# 17_RK3568_VO_Interface_1.net
KiCad netlist of a schematic drawn in Altium Designer
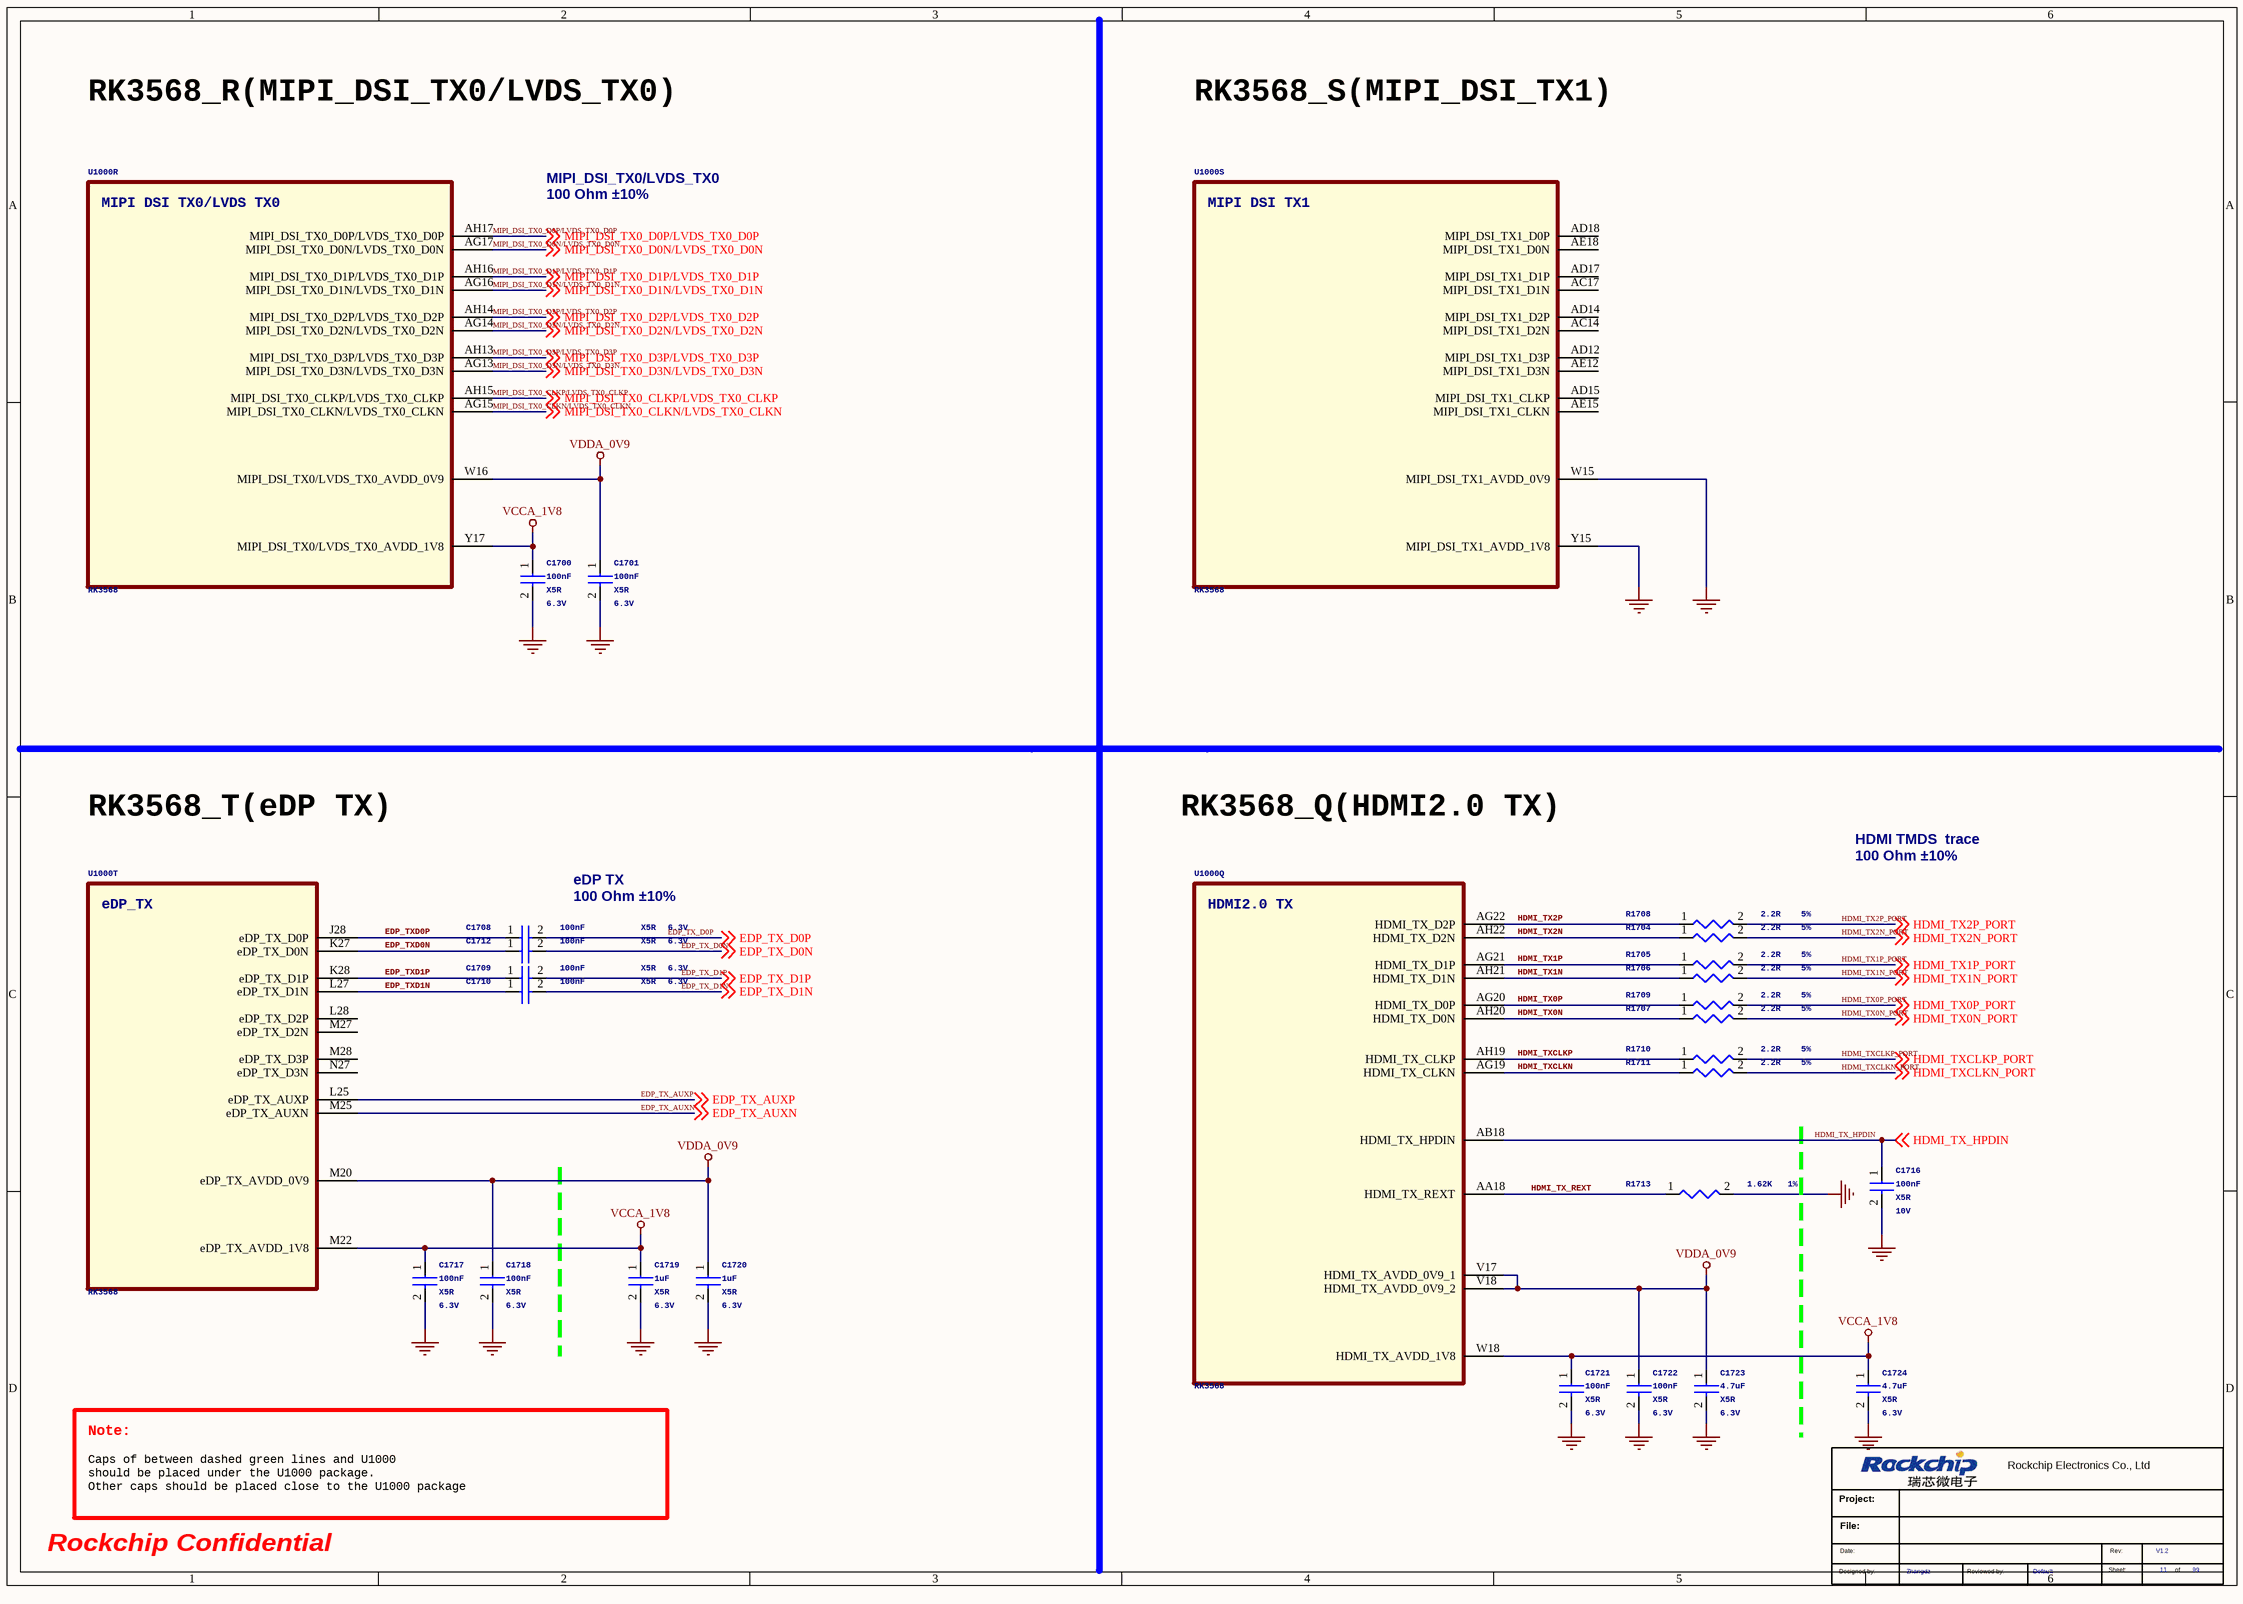
[diagram p0: 17.RK3568_VO Interface_1.SchDoc]

(export (version "E")
  (design (tool "Eeschema 10.0.6"))
  (components
    (comp (ref "*")
      (value "Rockchip_new")
      (fields
        (field (name "SCHEMATIC PAGE COUNT") "99")
        (field (name "SCHEMATIC PAGE NUMBER") "11")
        (field (name "DESIGNER") "Zhangdz")
        (field (name "REVISION") "V1.2")
        (field (name "CHECK") "Default")
      )
      (libsource (lib "*") (part "Rockchip_new"))
    )
    (comp (ref "C1700")
      (value "100nF")
      (footprint "C0201")
      (description "cap,100.00nF,+/-10%,6.3V,X5R,C0201")
      (fields
        (field (name "VOLTAGE") "6.3V")
        (field (name "DIELECTRIC") "X5R")
        (field (name "TOLERANCE") "10%")
        (field (name "MANUFACTURER") "TDK")
        (field (name "CREATED BY") "JJJ")
      )
      (libsource (lib "*") (part "CAP NP"))
    )
    (comp (ref "C1701")
      (value "100nF")
      (footprint "C0201")
      (description "cap,100.00nF,+/-10%,6.3V,X5R,C0201")
      (fields
        (field (name "VOLTAGE") "6.3V")
        (field (name "DIELECTRIC") "X5R")
        (field (name "MANUFACTURER") "TDK")
        (field (name "TOLERANCE") "10%")
        (field (name "CREATED BY") "JJJ")
      )
      (libsource (lib "*") (part "CAP NP"))
    )
    (comp (ref "C1708")
      (value "100nF")
      (footprint "C0201")
      (description "cap,100.00nF,+/-10%,6.3V,X5R,C0201")
      (fields
        (field (name "VOLTAGE") "6.3V")
        (field (name "DIELECTRIC") "X5R")
        (field (name "MANUFACTURER") "TDK")
        (field (name "TOLERANCE") "10%")
        (field (name "CREATED BY") "JJJ")
      )
      (libsource (lib "*") (part "CAP NP"))
    )
    (comp (ref "C1709")
      (value "100nF")
      (footprint "C0201")
      (description "cap,100.00nF,+/-10%,6.3V,X5R,C0201")
      (fields
        (field (name "VOLTAGE") "6.3V")
        (field (name "DIELECTRIC") "X5R")
        (field (name "MANUFACTURER") "TDK")
        (field (name "TOLERANCE") "10%")
        (field (name "CREATED BY") "JJJ")
      )
      (libsource (lib "*") (part "CAP NP"))
    )
    (comp (ref "C1710")
      (value "100nF")
      (footprint "C0201")
      (description "cap,100.00nF,+/-10%,6.3V,X5R,C0201")
      (fields
        (field (name "VOLTAGE") "6.3V")
        (field (name "DIELECTRIC") "X5R")
        (field (name "TOLERANCE") "10%")
        (field (name "MANUFACTURER") "TDK")
        (field (name "CREATED BY") "JJJ")
      )
      (libsource (lib "*") (part "CAP NP"))
    )
    (comp (ref "C1712")
      (value "100nF")
      (footprint "C0201")
      (description "cap,100.00nF,+/-10%,6.3V,X5R,C0201")
      (fields
        (field (name "VOLTAGE") "6.3V")
        (field (name "DIELECTRIC") "X5R")
        (field (name "TOLERANCE") "10%")
        (field (name "MANUFACTURER") "TDK")
        (field (name "CREATED BY") "JJJ")
      )
      (libsource (lib "*") (part "CAP NP"))
    )
    (comp (ref "C1716")
      (value "100nF")
      (footprint "C0402")
      (description "cap,100.00nF,+/-10%,10V,X5R,C0402")
      (fields
        (field (name "VOLTAGE") "10V")
        (field (name "DIELECTRIC") "X5R")
        (field (name "TOLERANCE") "10%")
        (field (name "MANUFACTURER") "TDK")
        (field (name "CREATED BY") "JJJ")
      )
      (libsource (lib "*") (part "CAP NP"))
    )
    (comp (ref "C1717")
      (value "100nF")
      (footprint "C0201")
      (description "cap,100.00nF,+/-10%,6.3V,X5R,C0201")
      (fields
        (field (name "VOLTAGE") "6.3V")
        (field (name "DIELECTRIC") "X5R")
        (field (name "TOLERANCE") "10%")
        (field (name "MANUFACTURER") "TDK")
        (field (name "CREATED BY") "JJJ")
      )
      (libsource (lib "*") (part "CAP NP"))
    )
    (comp (ref "C1718")
      (value "100nF")
      (footprint "C0201")
      (description "cap,100.00nF,+/-10%,6.3V,X5R,C0201")
      (fields
        (field (name "VOLTAGE") "6.3V")
        (field (name "DIELECTRIC") "X5R")
        (field (name "MANUFACTURER") "TDK")
        (field (name "TOLERANCE") "10%")
        (field (name "CREATED BY") "JJJ")
      )
      (libsource (lib "*") (part "CAP NP"))
    )
    (comp (ref "C1719")
      (value "1uF")
      (footprint "C0402")
      (description "cap,1.00uF,+/-10%,6.3V,X5R,C0402")
      (fields
        (field (name "VOLTAGE") "6.3V")
        (field (name "DIELECTRIC") "X5R")
        (field (name "TOLERANCE") "10%")
        (field (name "MANUFACTURER") "TDK")
        (field (name "CREATED BY") "JJJ")
      )
      (libsource (lib "*") (part "CAP NP"))
    )
    (comp (ref "C1720")
      (value "1uF")
      (footprint "C0402")
      (description "cap,1.00uF,+/-10%,6.3V,X5R,C0402")
      (fields
        (field (name "VOLTAGE") "6.3V")
        (field (name "DIELECTRIC") "X5R")
        (field (name "MANUFACTURER") "TDK")
        (field (name "TOLERANCE") "10%")
        (field (name "CREATED BY") "JJJ")
      )
      (libsource (lib "*") (part "CAP NP"))
    )
    (comp (ref "C1721")
      (value "100nF")
      (footprint "C0201")
      (description "cap,100.00nF,+/-10%,6.3V,X5R,C0201")
      (fields
        (field (name "VOLTAGE") "6.3V")
        (field (name "DIELECTRIC") "X5R")
        (field (name "MANUFACTURER") "TDK")
        (field (name "TOLERANCE") "10%")
        (field (name "CREATED BY") "JJJ")
      )
      (libsource (lib "*") (part "CAP NP"))
    )
    (comp (ref "C1722")
      (value "100nF")
      (footprint "C0201")
      (description "cap,100.00nF,+/-10%,6.3V,X5R,C0201")
      (fields
        (field (name "VOLTAGE") "6.3V")
        (field (name "DIELECTRIC") "X5R")
        (field (name "TOLERANCE") "10%")
        (field (name "MANUFACTURER") "TDK")
        (field (name "CREATED BY") "JJJ")
      )
      (libsource (lib "*") (part "CAP NP"))
    )
    (comp (ref "C1723")
      (value "4.7uF")
      (footprint "C0402")
      (description "cap,4.70uF,+/-10%,6.3V,X5R,C0402")
      (fields
        (field (name "VOLTAGE") "6.3V")
        (field (name "DIELECTRIC") "X5R")
        (field (name "TOLERANCE") "10%")
        (field (name "MANUFACTURER") "TDK")
        (field (name "CREATED BY") "JJJ")
      )
      (libsource (lib "*") (part "CAP NP"))
    )
    (comp (ref "C1724")
      (value "4.7uF")
      (footprint "C0402")
      (description "cap,4.70uF,+/-10%,6.3V,X5R,C0402")
      (fields
        (field (name "VOLTAGE") "6.3V")
        (field (name "DIELECTRIC") "X5R")
        (field (name "MANUFACTURER") "TDK")
        (field (name "TOLERANCE") "10%")
        (field (name "CREATED BY") "JJJ")
      )
      (libsource (lib "*") (part "CAP NP"))
    )
    (comp (ref "R1704")
      (value "2.2R")
      (footprint "R0402")
      (description "通用厚膜电阻,2R2,+/-5%,R0402,1/16W.")
      (fields
        (field (name "TOLERANCE") "5%")
        (field (name "MANUFACTURER") "YAGEO")
        (field (name "CREATED BY") "YTL")
      )
      (libsource (lib "*") (part "RESISTOR"))
    )
    (comp (ref "R1705")
      (value "2.2R")
      (footprint "R0402")
      (description "通用厚膜电阻,2R2,+/-5%,R0402,1/16W.")
      (fields
        (field (name "TOLERANCE") "5%")
        (field (name "MANUFACTURER") "YAGEO")
        (field (name "CREATED BY") "YTL")
      )
      (libsource (lib "*") (part "RESISTOR"))
    )
    (comp (ref "R1706")
      (value "2.2R")
      (footprint "R0402")
      (description "通用厚膜电阻,2R2,+/-5%,R0402,1/16W.")
      (fields
        (field (name "TOLERANCE") "5%")
        (field (name "MANUFACTURER") "YAGEO")
        (field (name "CREATED BY") "YTL")
      )
      (libsource (lib "*") (part "RESISTOR"))
    )
    (comp (ref "R1707")
      (value "2.2R")
      (footprint "R0402")
      (description "通用厚膜电阻,2R2,+/-5%,R0402,1/16W.")
      (fields
        (field (name "TOLERANCE") "5%")
        (field (name "MANUFACTURER") "YAGEO")
        (field (name "CREATED BY") "YTL")
      )
      (libsource (lib "*") (part "RESISTOR"))
    )
    (comp (ref "R1708")
      (value "2.2R")
      (footprint "R0402")
      (description "通用厚膜电阻,2R2,+/-5%,R0402,1/16W.")
      (fields
        (field (name "TOLERANCE") "5%")
        (field (name "MANUFACTURER") "YAGEO")
        (field (name "CREATED BY") "YTL")
      )
      (libsource (lib "*") (part "RESISTOR"))
    )
    (comp (ref "R1709")
      (value "2.2R")
      (footprint "R0402")
      (description "通用厚膜电阻,2R2,+/-5%,R0402,1/16W.")
      (fields
        (field (name "TOLERANCE") "5%")
        (field (name "MANUFACTURER") "YAGEO")
        (field (name "CREATED BY") "YTL")
      )
      (libsource (lib "*") (part "RESISTOR"))
    )
    (comp (ref "R1710")
      (value "2.2R")
      (footprint "R0402")
      (description "通用厚膜电阻,2R2,+/-5%,R0402,1/16W.")
      (fields
        (field (name "TOLERANCE") "5%")
        (field (name "MANUFACTURER") "YAGEO")
        (field (name "CREATED BY") "YTL")
      )
      (libsource (lib "*") (part "RESISTOR"))
    )
    (comp (ref "R1711")
      (value "2.2R")
      (footprint "R0402")
      (description "通用厚膜电阻,2R2,+/-5%,R0402,1/16W.")
      (fields
        (field (name "TOLERANCE") "5%")
        (field (name "MANUFACTURER") "YAGEO")
        (field (name "CREATED BY") "YTL")
      )
      (libsource (lib "*") (part "RESISTOR"))
    )
    (comp (ref "R1713")
      (value "1.62K")
      (footprint "R0201")
      (description "通用厚膜电阻,1K62,+/-1%,R0201,1/20W.")
      (fields
        (field (name "TOLERANCE") "1%")
        (field (name "MANUFACTURER") "YAGEO")
        (field (name "CREATED BY") "YTL")
      )
      (libsource (lib "*") (part "RESISTOR"))
    )
    (comp (ref "U1000")
      (value "RK3568")
      (footprint "BGA636_19R00X19R00X1R20")
      (description "ROCKCHIP SOC")
      (fields (field (name "MANUFACTURER") "Rockchip (瑞芯微)") (field (name "CREATED BY") "JJJ"))
      (libsource (lib "*") (part "SOC_RK3568"))
    )
  )
  (nets
    (net (code "1") (name "/EDP_TXD0N") (class "Default")
      (node (ref "C1712") (pin "1") (pinfunction "1_1") (pintype "passive"))
      (node (ref "U1000") (pin "K27") (pinfunction "eDP_TX_D0N_K27") (pintype "passive"))
    )
    (net (code "2") (name "/EDP_TXD0P") (class "Default")
      (node (ref "C1708") (pin "1") (pinfunction "1_1") (pintype "passive"))
      (node (ref "U1000") (pin "J28") (pinfunction "eDP_TX_D0P_J28") (pintype "passive"))
    )
    (net (code "3") (name "/EDP_TXD1N") (class "Default")
      (node (ref "C1710") (pin "1") (pinfunction "1_1") (pintype "passive"))
      (node (ref "U1000") (pin "L27") (pinfunction "eDP_TX_D1N_L27") (pintype "passive"))
    )
    (net (code "4") (name "/EDP_TXD1P") (class "Default")
      (node (ref "C1709") (pin "1") (pinfunction "1_1") (pintype "passive"))
      (node (ref "U1000") (pin "K28") (pinfunction "eDP_TX_D1P_K28") (pintype "passive"))
    )
    (net (code "5") (name "/HDMI_TX0N") (class "Default")
      (node (ref "R1707") (pin "1") (pinfunction "1_1") (pintype "passive"))
      (node (ref "U1000") (pin "AH20") (pinfunction "HDMI_TX_D0N_AH20") (pintype "passive"))
    )
    (net (code "6") (name "/HDMI_TX0P") (class "Default")
      (node (ref "R1709") (pin "1") (pinfunction "1_1") (pintype "passive"))
      (node (ref "U1000") (pin "AG20") (pinfunction "HDMI_TX_D0P_AG20") (pintype "passive"))
    )
    (net (code "7") (name "/HDMI_TX1N") (class "Default")
      (node (ref "R1706") (pin "1") (pinfunction "1_1") (pintype "passive"))
      (node (ref "U1000") (pin "AH21") (pinfunction "HDMI_TX_D1N_AH21") (pintype "passive"))
    )
    (net (code "8") (name "/HDMI_TX1P") (class "Default")
      (node (ref "R1705") (pin "1") (pinfunction "1_1") (pintype "passive"))
      (node (ref "U1000") (pin "AG21") (pinfunction "HDMI_TX_D1P_AG21") (pintype "passive"))
    )
    (net (code "9") (name "/HDMI_TX2N") (class "Default")
      (node (ref "R1704") (pin "1") (pinfunction "1_1") (pintype "passive"))
      (node (ref "U1000") (pin "AH22") (pinfunction "HDMI_TX_D2N_AH22") (pintype "passive"))
    )
    (net (code "10") (name "/HDMI_TX2P") (class "Default")
      (node (ref "R1708") (pin "1") (pinfunction "1_1") (pintype "passive"))
      (node (ref "U1000") (pin "AG22") (pinfunction "HDMI_TX_D2P_AG22") (pintype "passive"))
    )
    (net (code "11") (name "/HDMI_TXCLKN") (class "Default")
      (node (ref "R1711") (pin "1") (pinfunction "1_1") (pintype "passive"))
      (node (ref "U1000") (pin "AG19") (pinfunction "HDMI_TX_CLKN_AG19") (pintype "passive"))
    )
    (net (code "12") (name "/HDMI_TXCLKP") (class "Default")
      (node (ref "R1710") (pin "1") (pinfunction "1_1") (pintype "passive"))
      (node (ref "U1000") (pin "AH19") (pinfunction "HDMI_TX_CLKP_AH19") (pintype "passive"))
    )
    (net (code "13") (name "/HDMI_TX_REXT") (class "Default")
      (node (ref "R1713") (pin "1") (pinfunction "1_1") (pintype "passive"))
      (node (ref "U1000") (pin "AA18") (pinfunction "HDMI_TX_REXT_AA18") (pintype "passive"))
    )
    (net (code "14") (name "EDP_TX_AUXN") (class "Default")
      (node (ref "U1000") (pin "M25") (pinfunction "eDP_TX_AUXN_M25") (pintype "passive"))
    )
    (net (code "15") (name "EDP_TX_AUXP") (class "Default")
      (node (ref "U1000") (pin "L25") (pinfunction "eDP_TX_AUXP_L25") (pintype "passive"))
    )
    (net (code "16") (name "EDP_TX_D0N") (class "Default")
      (node (ref "C1712") (pin "2") (pinfunction "2_2") (pintype "passive"))
    )
    (net (code "17") (name "EDP_TX_D0P") (class "Default")
      (node (ref "C1708") (pin "2") (pinfunction "2_2") (pintype "passive"))
    )
    (net (code "18") (name "EDP_TX_D1N") (class "Default")
      (node (ref "C1710") (pin "2") (pinfunction "2_2") (pintype "passive"))
    )
    (net (code "19") (name "EDP_TX_D1P") (class "Default")
      (node (ref "C1709") (pin "2") (pinfunction "2_2") (pintype "passive"))
    )
    (net (code "20") (name "GND") (class "Default")
      (node (ref "C1700") (pin "2") (pinfunction "2_2") (pintype "passive"))
      (node (ref "C1701") (pin "2") (pinfunction "2_2") (pintype "passive"))
      (node (ref "C1716") (pin "2") (pinfunction "2_2") (pintype "passive"))
      (node (ref "C1717") (pin "2") (pinfunction "2_2") (pintype "passive"))
      (node (ref "C1718") (pin "2") (pinfunction "2_2") (pintype "passive"))
      (node (ref "C1719") (pin "2") (pinfunction "2_2") (pintype "passive"))
      (node (ref "C1720") (pin "2") (pinfunction "2_2") (pintype "passive"))
      (node (ref "C1721") (pin "2") (pinfunction "2_2") (pintype "passive"))
      (node (ref "C1722") (pin "2") (pinfunction "2_2") (pintype "passive"))
      (node (ref "C1723") (pin "2") (pinfunction "2_2") (pintype "passive"))
      (node (ref "C1724") (pin "2") (pinfunction "2_2") (pintype "passive"))
      (node (ref "R1713") (pin "2") (pinfunction "2_2") (pintype "passive"))
      (node (ref "U1000") (pin "W15") (pinfunction "MIPI_DSI_TX1_AVDD_0V9_W15") (pintype "passive"))
      (node (ref "U1000") (pin "Y15") (pinfunction "MIPI_DSI_TX1_AVDD_1V8_Y15") (pintype "passive"))
    )
    (net (code "21") (name "HDMI_TX0N_PORT") (class "Default")
      (node (ref "R1707") (pin "2") (pinfunction "2_2") (pintype "passive"))
    )
    (net (code "22") (name "HDMI_TX0P_PORT") (class "Default")
      (node (ref "R1709") (pin "2") (pinfunction "2_2") (pintype "passive"))
    )
    (net (code "23") (name "HDMI_TX1N_PORT") (class "Default")
      (node (ref "R1706") (pin "2") (pinfunction "2_2") (pintype "passive"))
    )
    (net (code "24") (name "HDMI_TX1P_PORT") (class "Default")
      (node (ref "R1705") (pin "2") (pinfunction "2_2") (pintype "passive"))
    )
    (net (code "25") (name "HDMI_TX2N_PORT") (class "Default")
      (node (ref "R1704") (pin "2") (pinfunction "2_2") (pintype "passive"))
    )
    (net (code "26") (name "HDMI_TX2P_PORT") (class "Default")
      (node (ref "R1708") (pin "2") (pinfunction "2_2") (pintype "passive"))
    )
    (net (code "27") (name "HDMI_TXCLKN_PORT") (class "Default")
      (node (ref "R1711") (pin "2") (pinfunction "2_2") (pintype "passive"))
    )
    (net (code "28") (name "HDMI_TXCLKP_PORT") (class "Default")
      (node (ref "R1710") (pin "2") (pinfunction "2_2") (pintype "passive"))
    )
    (net (code "29") (name "HDMI_TX_HPDIN") (class "Default")
      (node (ref "C1716") (pin "1") (pinfunction "1_1") (pintype "passive"))
      (node (ref "U1000") (pin "AB18") (pinfunction "HDMI_TX_HPDIN_AB18") (pintype "passive"))
    )
    (net (code "30") (name "MIPI_DSI_TX0_CLKN{slash}LVDS_TX0_CLKN") (class "Default")
      (node (ref "U1000") (pin "AG15") (pinfunction "MIPI_DSI_TX0_CLKN/LVDS_TX0_CLKN_AG15") (pintype "passive"))
    )
    (net (code "31") (name "MIPI_DSI_TX0_CLKP{slash}LVDS_TX0_CLKP") (class "Default")
      (node (ref "U1000") (pin "AH15") (pinfunction "MIPI_DSI_TX0_CLKP/LVDS_TX0_CLKP_AH15") (pintype "passive"))
    )
    (net (code "32") (name "MIPI_DSI_TX0_D0N{slash}LVDS_TX0_D0N") (class "Default")
      (node (ref "U1000") (pin "AG17") (pinfunction "MIPI_DSI_TX0_D0N/LVDS_TX0_D0N_AG17") (pintype "passive"))
    )
    (net (code "33") (name "MIPI_DSI_TX0_D0P{slash}LVDS_TX0_D0P") (class "Default")
      (node (ref "U1000") (pin "AH17") (pinfunction "MIPI_DSI_TX0_D0P/LVDS_TX0_D0P_AH17") (pintype "passive"))
    )
    (net (code "34") (name "MIPI_DSI_TX0_D1N{slash}LVDS_TX0_D1N") (class "Default")
      (node (ref "U1000") (pin "AG16") (pinfunction "MIPI_DSI_TX0_D1N/LVDS_TX0_D1N_AG16") (pintype "passive"))
    )
    (net (code "35") (name "MIPI_DSI_TX0_D1P{slash}LVDS_TX0_D1P") (class "Default")
      (node (ref "U1000") (pin "AH16") (pinfunction "MIPI_DSI_TX0_D1P/LVDS_TX0_D1P_AH16") (pintype "passive"))
    )
    (net (code "36") (name "MIPI_DSI_TX0_D2N{slash}LVDS_TX0_D2N") (class "Default")
      (node (ref "U1000") (pin "AG14") (pinfunction "MIPI_DSI_TX0_D2N/LVDS_TX0_D2N_AG14") (pintype "passive"))
    )
    (net (code "37") (name "MIPI_DSI_TX0_D2P{slash}LVDS_TX0_D2P") (class "Default")
      (node (ref "U1000") (pin "AH14") (pinfunction "MIPI_DSI_TX0_D2P/LVDS_TX0_D2P_AH14") (pintype "passive"))
    )
    (net (code "38") (name "MIPI_DSI_TX0_D3N{slash}LVDS_TX0_D3N") (class "Default")
      (node (ref "U1000") (pin "AG13") (pinfunction "MIPI_DSI_TX0_D3N/LVDS_TX0_D3N_AG13") (pintype "passive"))
    )
    (net (code "39") (name "MIPI_DSI_TX0_D3P{slash}LVDS_TX0_D3P") (class "Default")
      (node (ref "U1000") (pin "AH13") (pinfunction "MIPI_DSI_TX0_D3P/LVDS_TX0_D3P_AH13") (pintype "passive"))
    )
    (net (code "40") (name "VCCA_1V8") (class "Default")
      (node (ref "C1700") (pin "1") (pinfunction "1_1") (pintype "passive"))
      (node (ref "C1717") (pin "1") (pinfunction "1_1") (pintype "passive"))
      (node (ref "C1719") (pin "1") (pinfunction "1_1") (pintype "passive"))
      (node (ref "C1721") (pin "1") (pinfunction "1_1") (pintype "passive"))
      (node (ref "C1724") (pin "1") (pinfunction "1_1") (pintype "passive"))
      (node (ref "U1000") (pin "M22") (pinfunction "eDP_TX_AVDD_1V8_M22") (pintype "passive"))
      (node (ref "U1000") (pin "W18") (pinfunction "HDMI_TX_AVDD_1V8_W18") (pintype "passive"))
      (node (ref "U1000") (pin "Y17") (pinfunction "MIPI_DSI_TX0/LVDS_TX0_AVDD_1V8_Y17") (pintype "passive"))
    )
    (net (code "41") (name "VDDA_0V9") (class "Default")
      (node (ref "C1701") (pin "1") (pinfunction "1_1") (pintype "passive"))
      (node (ref "C1718") (pin "1") (pinfunction "1_1") (pintype "passive"))
      (node (ref "C1720") (pin "1") (pinfunction "1_1") (pintype "passive"))
      (node (ref "C1722") (pin "1") (pinfunction "1_1") (pintype "passive"))
      (node (ref "C1723") (pin "1") (pinfunction "1_1") (pintype "passive"))
      (node (ref "U1000") (pin "M20") (pinfunction "eDP_TX_AVDD_0V9_M20") (pintype "passive"))
      (node (ref "U1000") (pin "V17") (pinfunction "HDMI_TX_AVDD_0V9_1_V17") (pintype "passive"))
      (node (ref "U1000") (pin "V18") (pinfunction "HDMI_TX_AVDD_0V9_2_V18") (pintype "passive"))
      (node (ref "U1000") (pin "W16") (pinfunction "MIPI_DSI_TX0/LVDS_TX0_AVDD_0V9_W16") (pintype "passive"))
    )
    (net (code "42") (name "unconnected-(U1000S-MIPI_DSI_TX1_CLKN-PadAE15)") (class "Default")
      (node (ref "U1000") (pin "AE15") (pinfunction "MIPI_DSI_TX1_CLKN_AE15") (pintype "passive"))
    )
    (net (code "43") (name "unconnected-(U1000S-MIPI_DSI_TX1_CLKP-PadAD15)") (class "Default")
      (node (ref "U1000") (pin "AD15") (pinfunction "MIPI_DSI_TX1_CLKP_AD15") (pintype "passive"))
    )
    (net (code "44") (name "unconnected-(U1000S-MIPI_DSI_TX1_D0N-PadAE18)") (class "Default")
      (node (ref "U1000") (pin "AE18") (pinfunction "MIPI_DSI_TX1_D0N_AE18") (pintype "passive"))
    )
    (net (code "45") (name "unconnected-(U1000S-MIPI_DSI_TX1_D0P-PadAD18)") (class "Default")
      (node (ref "U1000") (pin "AD18") (pinfunction "MIPI_DSI_TX1_D0P_AD18") (pintype "passive"))
    )
    (net (code "46") (name "unconnected-(U1000S-MIPI_DSI_TX1_D1N-PadAC17)") (class "Default")
      (node (ref "U1000") (pin "AC17") (pinfunction "MIPI_DSI_TX1_D1N_AC17") (pintype "passive"))
    )
    (net (code "47") (name "unconnected-(U1000S-MIPI_DSI_TX1_D1P-PadAD17)") (class "Default")
      (node (ref "U1000") (pin "AD17") (pinfunction "MIPI_DSI_TX1_D1P_AD17") (pintype "passive"))
    )
    (net (code "48") (name "unconnected-(U1000S-MIPI_DSI_TX1_D2N-PadAC14)") (class "Default")
      (node (ref "U1000") (pin "AC14") (pinfunction "MIPI_DSI_TX1_D2N_AC14") (pintype "passive"))
    )
    (net (code "49") (name "unconnected-(U1000S-MIPI_DSI_TX1_D2P-PadAD14)") (class "Default")
      (node (ref "U1000") (pin "AD14") (pinfunction "MIPI_DSI_TX1_D2P_AD14") (pintype "passive"))
    )
    (net (code "50") (name "unconnected-(U1000S-MIPI_DSI_TX1_D3N-PadAE12)") (class "Default")
      (node (ref "U1000") (pin "AE12") (pinfunction "MIPI_DSI_TX1_D3N_AE12") (pintype "passive"))
    )
    (net (code "51") (name "unconnected-(U1000S-MIPI_DSI_TX1_D3P-PadAD12)") (class "Default")
      (node (ref "U1000") (pin "AD12") (pinfunction "MIPI_DSI_TX1_D3P_AD12") (pintype "passive"))
    )
    (net (code "52") (name "unconnected-(U1000T-eDP_TX_D2N-PadM27)") (class "Default")
      (node (ref "U1000") (pin "M27") (pinfunction "eDP_TX_D2N_M27") (pintype "passive"))
    )
    (net (code "53") (name "unconnected-(U1000T-eDP_TX_D2P-PadL28)") (class "Default")
      (node (ref "U1000") (pin "L28") (pinfunction "eDP_TX_D2P_L28") (pintype "passive"))
    )
    (net (code "54") (name "unconnected-(U1000T-eDP_TX_D3N-PadN27)") (class "Default")
      (node (ref "U1000") (pin "N27") (pinfunction "eDP_TX_D3N_N27") (pintype "passive"))
    )
    (net (code "55") (name "unconnected-(U1000T-eDP_TX_D3P-PadM28)") (class "Default")
      (node (ref "U1000") (pin "M28") (pinfunction "eDP_TX_D3P_M28") (pintype "passive"))
    )
  )
)
